# CM_Nightfall-Air_v1.net
KiCad netlist of a schematic drawn in EAGLE
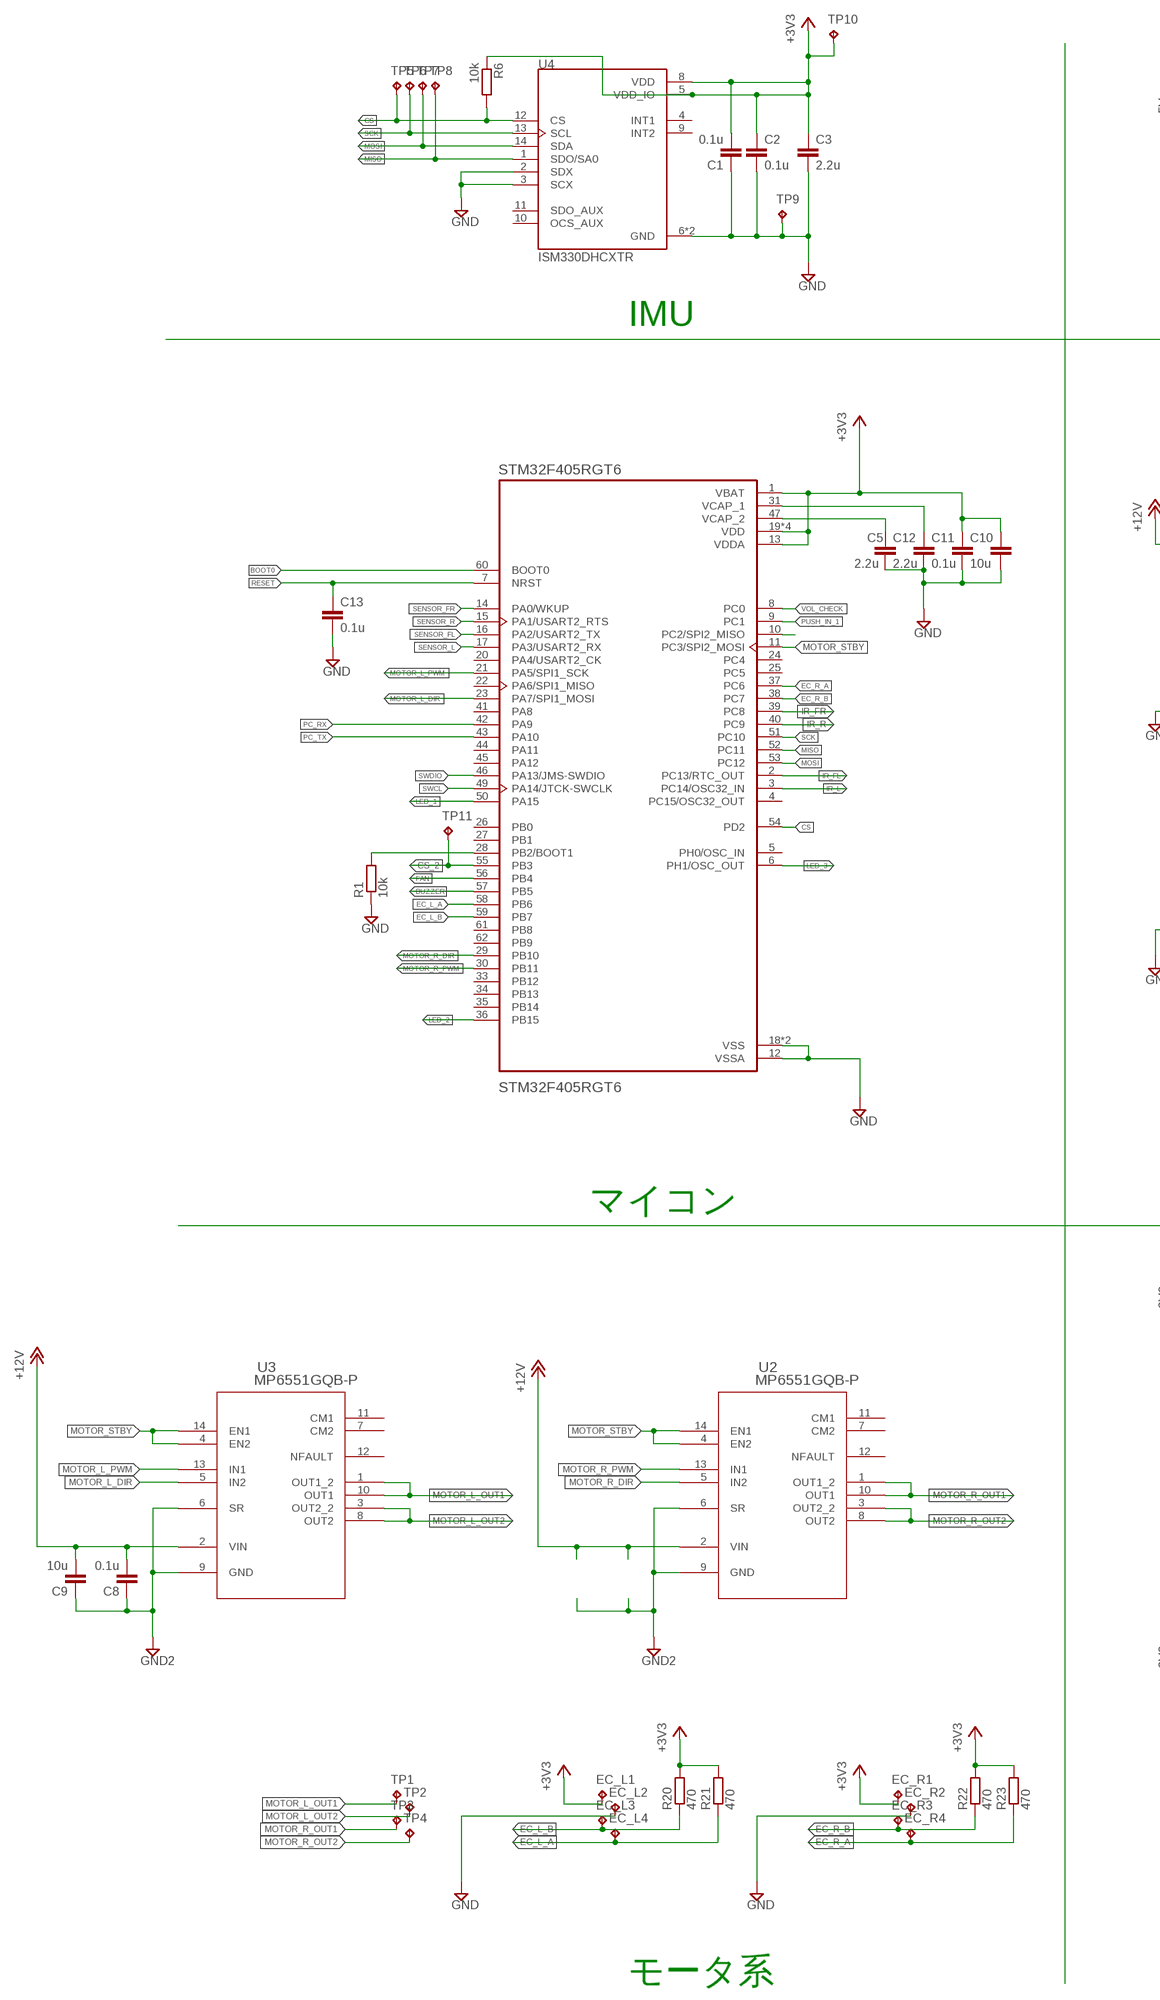
[diagram p0: schematic, sheet 1, part 1 of 2]
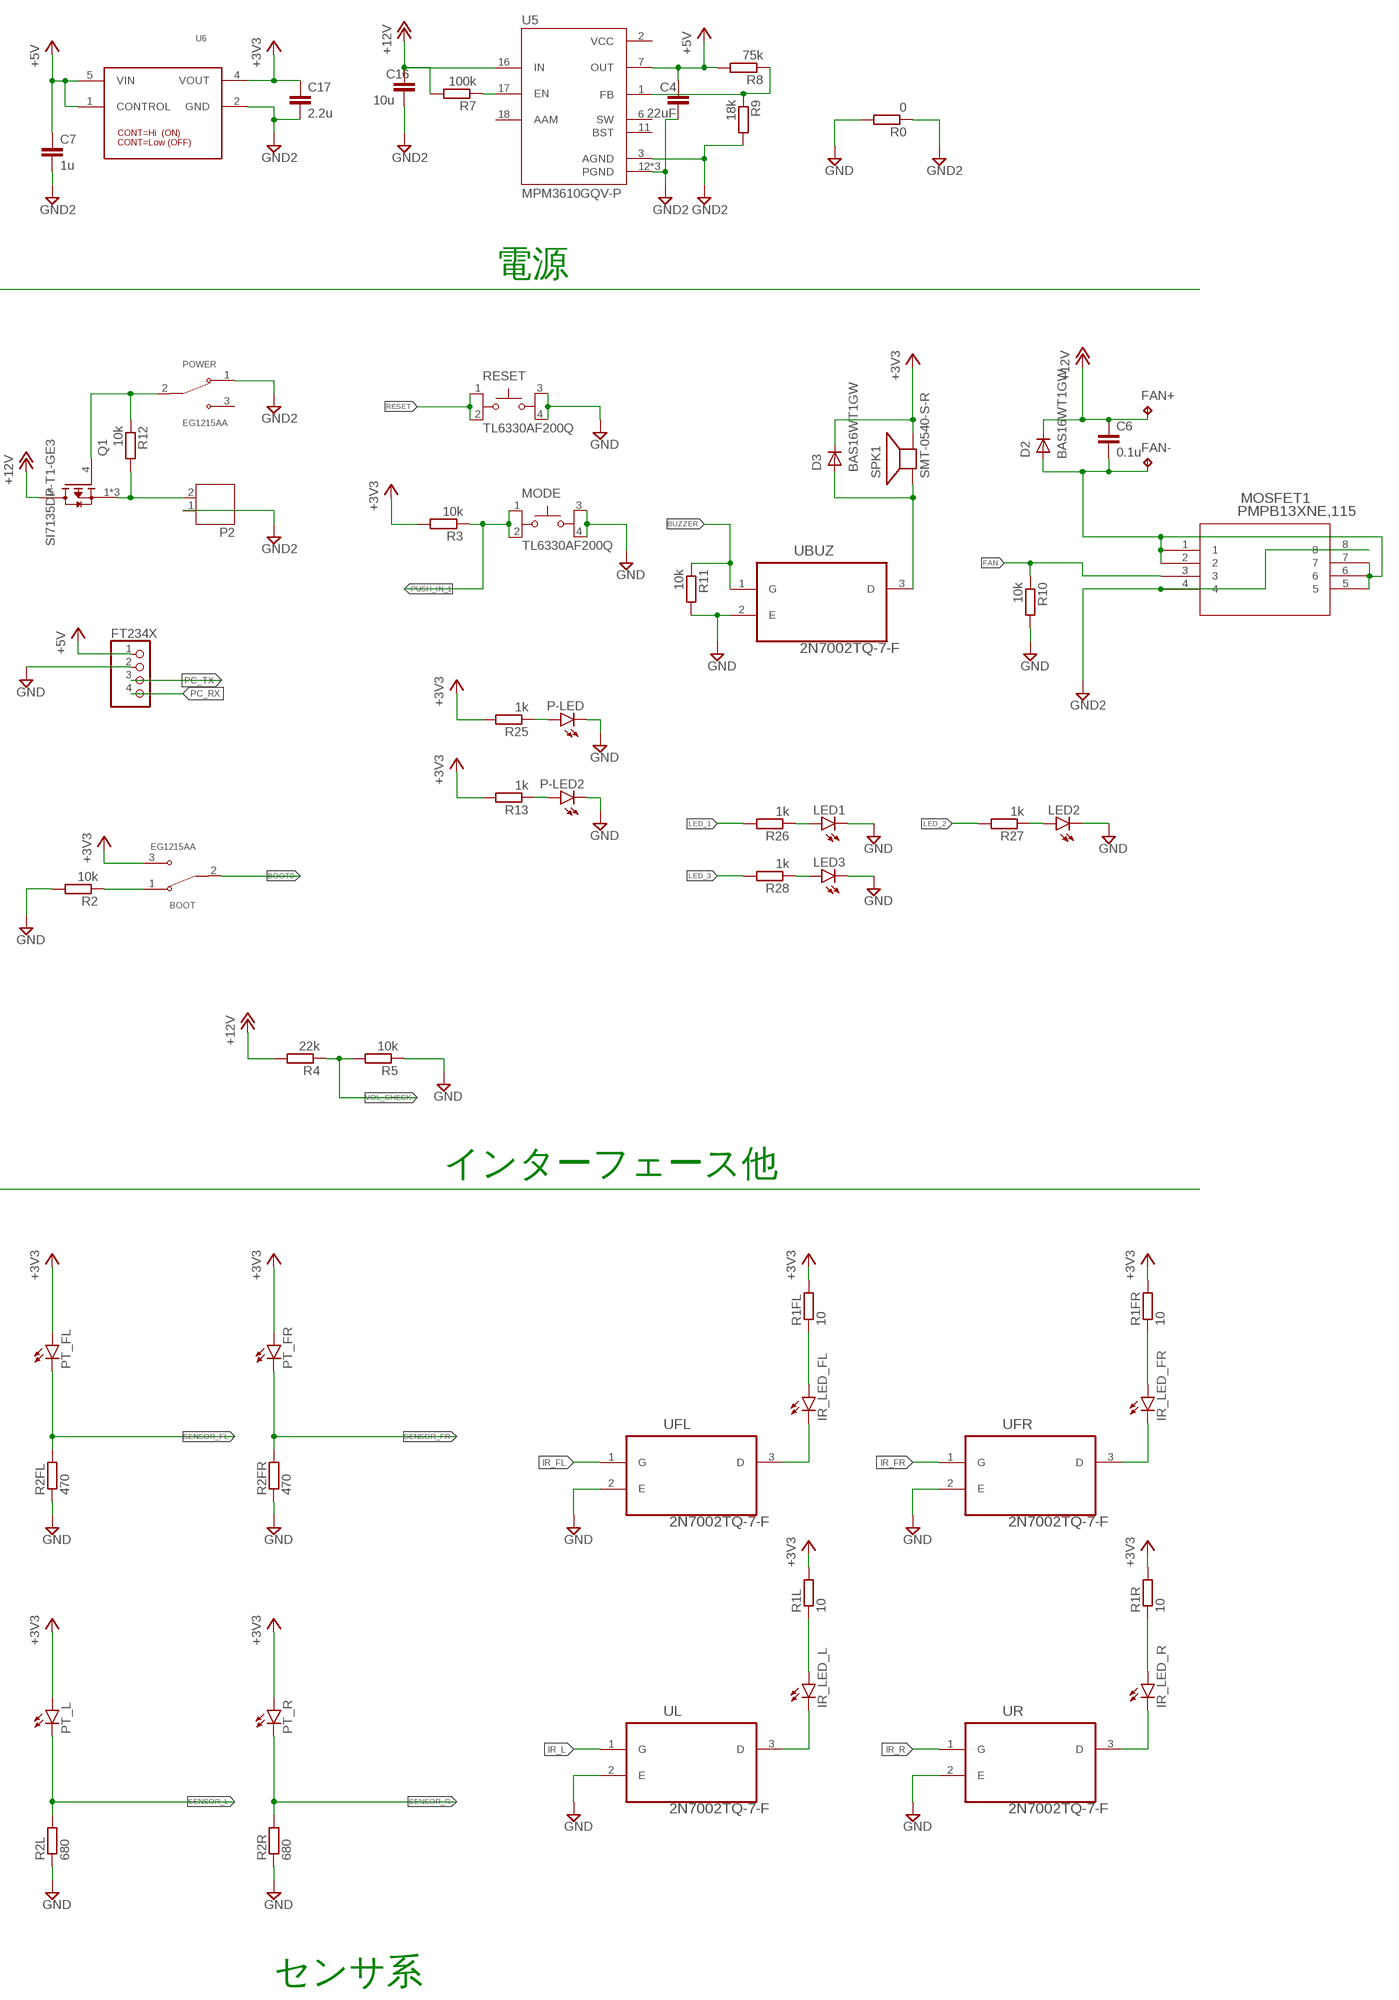
[diagram p1: schematic, sheet 1, part 2 of 2]

(export (version "E")
  (design (tool "Eeschema 10.0.6"))
  (components
    (comp (ref "BOOT")
      (value "EG1215AA")
      (footprint "eagle-import:SW_EG1215AA")
      (fields (field (name "MF") "E-Switch"))
      (libsource (lib "eagle-import") (part "EG1215AA"))
    )
    (comp (ref "C1")
      (value "0.1u")
      (footprint "eagle-import:C0402")
      (libsource (lib "eagle-import") (part "C-EUC0402"))
    )
    (comp (ref "C2")
      (value "0.1u")
      (footprint "eagle-import:C0402")
      (libsource (lib "eagle-import") (part "C-EUC0402"))
    )
    (comp (ref "C3")
      (value "2.2u")
      (footprint "eagle-import:C0402")
      (libsource (lib "eagle-import") (part "C-EUC0402"))
    )
    (comp (ref "C4")
      (value "22uF")
      (footprint "eagle-import:C0402")
      (libsource (lib "eagle-import") (part "C-EUC0402"))
    )
    (comp (ref "C5")
      (value "2.2u")
      (footprint "eagle-import:C0402")
      (libsource (lib "eagle-import") (part "C-EUC0402"))
    )
    (comp (ref "C6")
      (value "0.1u")
      (footprint "eagle-import:C0402")
      (libsource (lib "eagle-import") (part "C-EUC0402"))
    )
    (comp (ref "C7")
      (value "1u")
      (footprint "eagle-import:C0402")
      (libsource (lib "eagle-import") (part "C-EUC0402"))
    )
    (comp (ref "C8")
      (value "0.1u")
      (footprint "eagle-import:C0402")
      (libsource (lib "eagle-import") (part "C-EUC0402"))
    )
    (comp (ref "C9")
      (value "10u")
      (footprint "eagle-import:C0402")
      (libsource (lib "eagle-import") (part "C-EUC0402"))
    )
    (comp (ref "C10")
      (value "10u")
      (footprint "eagle-import:C0402")
      (libsource (lib "eagle-import") (part "C-EUC0402"))
    )
    (comp (ref "C11")
      (value "0.1u")
      (footprint "eagle-import:C0402")
      (libsource (lib "eagle-import") (part "C-EUC0402"))
    )
    (comp (ref "C12")
      (value "2.2u")
      (footprint "eagle-import:C0402")
      (libsource (lib "eagle-import") (part "C-EUC0402"))
    )
    (comp (ref "C13")
      (value "0.1u")
      (footprint "eagle-import:C0402")
      (libsource (lib "eagle-import") (part "C-EUC0402"))
    )
    (comp (ref "C16")
      (value "10u")
      (footprint "eagle-import:C0402")
      (libsource (lib "eagle-import") (part "C-EUC0402"))
    )
    (comp (ref "C17")
      (value "2.2u")
      (footprint "eagle-import:C0402")
      (libsource (lib "eagle-import") (part "C-EUC0402"))
    )
    (comp (ref "D2")
      (value "BAS16WT1GW")
      (footprint "eagle-import:SOT323")
      (fields (field (name "MF") "ON Semiconductor") (field (name "MP") "BAS16WT1G"))
      (libsource (lib "eagle-import") (part "BAS16WT1GW"))
    )
    (comp (ref "D3")
      (value "BAS16WT1GW")
      (footprint "eagle-import:SOT323")
      (fields (field (name "MF") "ON Semiconductor") (field (name "MP") "BAS16WT1G"))
      (libsource (lib "eagle-import") (part "BAS16WT1GW"))
    )
    (comp (ref "EC_L1")
      (value "TPB1,27")
      (footprint "eagle-import:B1,27")
      (libsource (lib "eagle-import") (part "TPB1,27"))
    )
    (comp (ref "EC_L2")
      (value "TPB1,27")
      (footprint "eagle-import:B1,27")
      (libsource (lib "eagle-import") (part "TPB1,27"))
    )
    (comp (ref "EC_L3")
      (value "TPB1,27")
      (footprint "eagle-import:B1,27")
      (libsource (lib "eagle-import") (part "TPB1,27"))
    )
    (comp (ref "EC_L4")
      (value "TPB1,27")
      (footprint "eagle-import:B1,27")
      (libsource (lib "eagle-import") (part "TPB1,27"))
    )
    (comp (ref "EC_R1")
      (value "TPB1,27")
      (footprint "eagle-import:B1,27")
      (libsource (lib "eagle-import") (part "TPB1,27"))
    )
    (comp (ref "EC_R2")
      (value "TPB1,27")
      (footprint "eagle-import:B1,27")
      (libsource (lib "eagle-import") (part "TPB1,27"))
    )
    (comp (ref "EC_R3")
      (value "TPB1,27")
      (footprint "eagle-import:B1,27")
      (libsource (lib "eagle-import") (part "TPB1,27"))
    )
    (comp (ref "EC_R4")
      (value "TPB1,27")
      (footprint "eagle-import:B1,27")
      (libsource (lib "eagle-import") (part "TPB1,27"))
    )
    (comp (ref "FAN+")
      (value "TPB1,27")
      (footprint "eagle-import:B1,27")
      (libsource (lib "eagle-import") (part "TPB1,27"))
    )
    (comp (ref "FAN-")
      (value "TPB1,27")
      (footprint "eagle-import:B1,27")
      (libsource (lib "eagle-import") (part "TPB1,27"))
    )
    (comp (ref "FT234X")
      (value "PINHD-1X4")
      (footprint "eagle-import:1X04")
      (libsource (lib "eagle-import") (part "PINHD-1X4"))
    )
    (comp (ref "IR_LED_FL")
      (value "LED5MM")
      (footprint "eagle-import:LED5MM")
      (libsource (lib "eagle-import") (part "LED5MM"))
    )
    (comp (ref "IR_LED_FR")
      (value "LED5MM")
      (footprint "eagle-import:LED5MM")
      (libsource (lib "eagle-import") (part "LED5MM"))
    )
    (comp (ref "IR_LED_L")
      (value "LED5MM")
      (footprint "eagle-import:LED5MM")
      (libsource (lib "eagle-import") (part "LED5MM"))
    )
    (comp (ref "IR_LED_R")
      (value "LED5MM")
      (footprint "eagle-import:LED5MM")
      (libsource (lib "eagle-import") (part "LED5MM"))
    )
    (comp (ref "LED1")
      (value "LEDCHIPLED_0603")
      (footprint "eagle-import:CHIPLED_0603")
      (libsource (lib "eagle-import") (part "LEDCHIPLED_0603"))
    )
    (comp (ref "LED2")
      (value "LEDCHIPLED_0603")
      (footprint "eagle-import:CHIPLED_0603")
      (libsource (lib "eagle-import") (part "LEDCHIPLED_0603"))
    )
    (comp (ref "LED3")
      (value "LEDCHIPLED_0603")
      (footprint "eagle-import:CHIPLED_0603")
      (libsource (lib "eagle-import") (part "LEDCHIPLED_0603"))
    )
    (comp (ref "MODE")
      (value "TL6330AF200Q")
      (footprint "eagle-import:SW_TL6330AF200Q")
      (fields (field (name "MF") "E-Switch"))
      (libsource (lib "eagle-import") (part "TL6330AF200Q"))
    )
    (comp (ref "MOSFET1")
      (value "PMPB13XNE,115")
      (footprint "eagle-import:DFN2020MD-6_SOT1220_NEX")
      (fields (field (name "COPYRIGHT") "Copyright (C) 2025 Ultra Librarian. All rights reserved."))
      (libsource (lib "eagle-import") (part "PMPB13XNE,115"))
    )
    (comp (ref "P-LED")
      (value "LEDCHIPLED_0603")
      (footprint "eagle-import:CHIPLED_0603")
      (libsource (lib "eagle-import") (part "LEDCHIPLED_0603"))
    )
    (comp (ref "P-LED2")
      (value "LEDCHIPLED_0603")
      (footprint "eagle-import:CHIPLED_0603")
      (libsource (lib "eagle-import") (part "LEDCHIPLED_0603"))
    )
    (comp (ref "P2")
      (value "JST-PH2")
      (footprint "eagle-import:JST-PH2")
      (libsource (lib "eagle-import") (part "JST-PH2"))
    )
    (comp (ref "POWER")
      (value "EG1215AA")
      (footprint "eagle-import:SW_EG1215AA")
      (fields (field (name "MF") "E-Switch"))
      (libsource (lib "eagle-import") (part "EG1215AA"))
    )
    (comp (ref "PT_FL")
      (value "LED5MM")
      (footprint "eagle-import:LED5MM")
      (libsource (lib "eagle-import") (part "LED5MM"))
    )
    (comp (ref "PT_FR")
      (value "LED5MM")
      (footprint "eagle-import:LED5MM")
      (libsource (lib "eagle-import") (part "LED5MM"))
    )
    (comp (ref "PT_L")
      (value "LED5MM")
      (footprint "eagle-import:LED5MM")
      (libsource (lib "eagle-import") (part "LED5MM"))
    )
    (comp (ref "PT_R")
      (value "LED5MM")
      (footprint "eagle-import:LED5MM")
      (libsource (lib "eagle-import") (part "LED5MM"))
    )
    (comp (ref "Q1")
      (value "SI7135DP-T1-GE3")
      (footprint "eagle-import:TRANS_SI7135DP-T1-GE3")
      (fields (field (name "MANUFACTURER") "Vishay Siliconix"))
      (libsource (lib "eagle-import") (part "SI7135DP-T1-GE3"))
    )
    (comp (ref "R0")
      (value "0")
      (footprint "eagle-import:R0402")
      (libsource (lib "eagle-import") (part "R-EU_R0402"))
    )
    (comp (ref "R1")
      (value "10k")
      (footprint "eagle-import:R0402")
      (libsource (lib "eagle-import") (part "R-EU_R0402"))
    )
    (comp (ref "R1FL")
      (value "10")
      (footprint "eagle-import:R0402")
      (libsource (lib "eagle-import") (part "R-EU_R0402"))
    )
    (comp (ref "R1FR")
      (value "10")
      (footprint "eagle-import:R0402")
      (libsource (lib "eagle-import") (part "R-EU_R0402"))
    )
    (comp (ref "R1L")
      (value "10")
      (footprint "eagle-import:R0402")
      (libsource (lib "eagle-import") (part "R-EU_R0402"))
    )
    (comp (ref "R1R")
      (value "10")
      (footprint "eagle-import:R0402")
      (libsource (lib "eagle-import") (part "R-EU_R0402"))
    )
    (comp (ref "R2")
      (value "10k")
      (footprint "eagle-import:R0402")
      (libsource (lib "eagle-import") (part "R-EU_R0402"))
    )
    (comp (ref "R2FL")
      (value "470")
      (footprint "eagle-import:R0402")
      (libsource (lib "eagle-import") (part "R-EU_R0402"))
    )
    (comp (ref "R2FR")
      (value "470")
      (footprint "eagle-import:R0402")
      (libsource (lib "eagle-import") (part "R-EU_R0402"))
    )
    (comp (ref "R2L")
      (value "680")
      (footprint "eagle-import:R0402")
      (libsource (lib "eagle-import") (part "R-EU_R0402"))
    )
    (comp (ref "R2R")
      (value "680")
      (footprint "eagle-import:R0402")
      (libsource (lib "eagle-import") (part "R-EU_R0402"))
    )
    (comp (ref "R3")
      (value "10k")
      (footprint "eagle-import:R0402")
      (libsource (lib "eagle-import") (part "R-EU_R0402"))
    )
    (comp (ref "R4")
      (value "22k")
      (footprint "eagle-import:R0402")
      (libsource (lib "eagle-import") (part "R-EU_R0402"))
    )
    (comp (ref "R5")
      (value "10k")
      (footprint "eagle-import:R0402")
      (libsource (lib "eagle-import") (part "R-EU_R0402"))
    )
    (comp (ref "R6")
      (value "10k")
      (footprint "eagle-import:R0402")
      (libsource (lib "eagle-import") (part "R-EU_R0402"))
    )
    (comp (ref "R7")
      (value "100k")
      (footprint "eagle-import:R0402")
      (libsource (lib "eagle-import") (part "R-EU_R0402"))
    )
    (comp (ref "R8")
      (value "75k")
      (footprint "eagle-import:R0402")
      (libsource (lib "eagle-import") (part "R-EU_R0402"))
    )
    (comp (ref "R9")
      (value "18k")
      (footprint "eagle-import:R0402")
      (libsource (lib "eagle-import") (part "R-EU_R0402"))
    )
    (comp (ref "R10")
      (value "10k")
      (footprint "eagle-import:R0402")
      (libsource (lib "eagle-import") (part "R-EU_R0402"))
    )
    (comp (ref "R11")
      (value "10k")
      (footprint "eagle-import:R0402")
      (libsource (lib "eagle-import") (part "R-EU_R0402"))
    )
    (comp (ref "R12")
      (value "10k")
      (footprint "eagle-import:R0402")
      (libsource (lib "eagle-import") (part "R-EU_R0402"))
    )
    (comp (ref "R13")
      (value "1k")
      (footprint "eagle-import:R0402")
      (libsource (lib "eagle-import") (part "R-EU_R0402"))
    )
    (comp (ref "R20")
      (value "470")
      (footprint "eagle-import:R0402")
      (libsource (lib "eagle-import") (part "R-EU_R0402"))
    )
    (comp (ref "R21")
      (value "470")
      (footprint "eagle-import:R0402")
      (libsource (lib "eagle-import") (part "R-EU_R0402"))
    )
    (comp (ref "R22")
      (value "470")
      (footprint "eagle-import:R0402")
      (libsource (lib "eagle-import") (part "R-EU_R0402"))
    )
    (comp (ref "R23")
      (value "470")
      (footprint "eagle-import:R0402")
      (libsource (lib "eagle-import") (part "R-EU_R0402"))
    )
    (comp (ref "R25")
      (value "1k")
      (footprint "eagle-import:R0402")
      (libsource (lib "eagle-import") (part "R-EU_R0402"))
    )
    (comp (ref "R26")
      (value "1k")
      (footprint "eagle-import:R0402")
      (libsource (lib "eagle-import") (part "R-EU_R0402"))
    )
    (comp (ref "R27")
      (value "1k")
      (footprint "eagle-import:R0402")
      (libsource (lib "eagle-import") (part "R-EU_R0402"))
    )
    (comp (ref "R28")
      (value "1k")
      (footprint "eagle-import:R0402")
      (libsource (lib "eagle-import") (part "R-EU_R0402"))
    )
    (comp (ref "RESET")
      (value "TL6330AF200Q")
      (footprint "eagle-import:SW_TL6330AF200Q")
      (fields (field (name "MF") "E-Switch"))
      (libsource (lib "eagle-import") (part "TL6330AF200Q"))
    )
    (comp (ref "SPK1")
      (value "SMT-0540-S-R")
      (footprint "eagle-import:SMT-0540-S-R")
      (fields (field (name "DIGI-KEY_PART_NUMBER") "668-1060-1-ND") (field (name "MF") "PUI"))
      (libsource (lib "eagle-import") (part "SMT-0540-S-R"))
    )
    (comp (ref "STM32F405RGT6")
      (value "STM32F405RGT6")
      (footprint "eagle-import:QFP50P1200X1200X160-64N")
      (fields (field (name "MF") "STMicroelectronics"))
      (libsource (lib "eagle-import") (part "STM32F405RGT6"))
    )
    (comp (ref "TP1")
      (value "TPB1,27")
      (footprint "eagle-import:B1,27")
      (libsource (lib "eagle-import") (part "TPB1,27"))
    )
    (comp (ref "TP2")
      (value "TPB1,27")
      (footprint "eagle-import:B1,27")
      (libsource (lib "eagle-import") (part "TPB1,27"))
    )
    (comp (ref "TP3")
      (value "TPB1,27")
      (footprint "eagle-import:B1,27")
      (libsource (lib "eagle-import") (part "TPB1,27"))
    )
    (comp (ref "TP4")
      (value "TPB1,27")
      (footprint "eagle-import:B1,27")
      (libsource (lib "eagle-import") (part "TPB1,27"))
    )
    (comp (ref "TP5")
      (value "TPTP06R")
      (footprint "eagle-import:TP06R")
      (libsource (lib "eagle-import") (part "TPTP06R"))
    )
    (comp (ref "TP6")
      (value "TPTP06R")
      (footprint "eagle-import:TP06R")
      (libsource (lib "eagle-import") (part "TPTP06R"))
    )
    (comp (ref "TP7")
      (value "TPTP06R")
      (footprint "eagle-import:TP06R")
      (libsource (lib "eagle-import") (part "TPTP06R"))
    )
    (comp (ref "TP8")
      (value "TPTP06R")
      (footprint "eagle-import:TP06R")
      (libsource (lib "eagle-import") (part "TPTP06R"))
    )
    (comp (ref "TP9")
      (value "TPTP06R")
      (footprint "eagle-import:TP06R")
      (libsource (lib "eagle-import") (part "TPTP06R"))
    )
    (comp (ref "TP10")
      (value "TPTP06R")
      (footprint "eagle-import:TP06R")
      (libsource (lib "eagle-import") (part "TPTP06R"))
    )
    (comp (ref "TP11")
      (value "TPTP06R")
      (footprint "eagle-import:TP06R")
      (libsource (lib "eagle-import") (part "TPTP06R"))
    )
    (comp (ref "U2")
      (value "MP6551GQB-P")
      (footprint "eagle-import:QFN-14_MP6551_MNP")
      (fields (field (name "COPYRIGHT") "Copyright (C) 2025 Ultra Librarian. All rights reserved."))
      (libsource (lib "eagle-import") (part "MP6551GQB-P"))
    )
    (comp (ref "U3")
      (value "MP6551GQB-P")
      (footprint "eagle-import:QFN-14_MP6551_MNP")
      (fields (field (name "COPYRIGHT") "Copyright (C) 2025 Ultra Librarian. All rights reserved."))
      (libsource (lib "eagle-import") (part "MP6551GQB-P"))
    )
    (comp (ref "U4")
      (value "ISM330DHCXTR")
      (footprint "eagle-import:PQFN50P250X300X86-14N")
      (fields (field (name "MF") "STMicroelectronics"))
      (libsource (lib "eagle-import") (part "ISM330DHCXTR"))
    )
    (comp (ref "U5")
      (value "MPM3610GQV-P")
      (footprint "eagle-import:CONV_MPM3610GQV-P")
      (fields (field (name "MF") "Monolithic Power Systems") (field (name "MP") "MPM3610GQVP"))
      (libsource (lib "eagle-import") (part "MPM3610GQV-P"))
    )
    (comp (ref "U6")
      (value "I-10673_NJM2884U1-33")
      (footprint "eagle-import:NJM2884U1-33")
      (libsource (lib "eagle-import") (part "I-10673_NJM2884U1-33"))
    )
    (comp (ref "UBUZ")
      (value "2N7002TQ-7-F")
      (footprint "eagle-import:SOT50P160X90-3N")
      (fields (field (name "MF") "Diodes Inc."))
      (libsource (lib "eagle-import") (part "2N7002TQ-7-F"))
    )
    (comp (ref "UFL")
      (value "2N7002TQ-7-F")
      (footprint "eagle-import:SOT50P160X90-3N")
      (fields (field (name "MF") "Diodes Inc."))
      (libsource (lib "eagle-import") (part "2N7002TQ-7-F"))
    )
    (comp (ref "UFR")
      (value "2N7002TQ-7-F")
      (footprint "eagle-import:SOT50P160X90-3N")
      (fields (field (name "MF") "Diodes Inc."))
      (libsource (lib "eagle-import") (part "2N7002TQ-7-F"))
    )
    (comp (ref "UL")
      (value "2N7002TQ-7-F")
      (footprint "eagle-import:SOT50P160X90-3N")
      (fields (field (name "MF") "Diodes Inc."))
      (libsource (lib "eagle-import") (part "2N7002TQ-7-F"))
    )
    (comp (ref "UR")
      (value "2N7002TQ-7-F")
      (footprint "eagle-import:SOT50P160X90-3N")
      (fields (field (name "MF") "Diodes Inc."))
      (libsource (lib "eagle-import") (part "2N7002TQ-7-F"))
    )
  )
  (nets
    (net (code "1") (name "+3V3") (class "Default")
      (node (ref "BOOT") (pin "3") (pinfunction "3_3") (pintype "passive"))
      (node (ref "C1") (pin "2") (pinfunction "2_2") (pintype "passive"))
      (node (ref "C10") (pin "1") (pinfunction "1_1") (pintype "passive"))
      (node (ref "C11") (pin "1") (pinfunction "1_1") (pintype "passive"))
      (node (ref "C17") (pin "1") (pinfunction "1_1") (pintype "passive"))
      (node (ref "C2") (pin "1") (pinfunction "1_1") (pintype "passive"))
      (node (ref "C3") (pin "1") (pinfunction "1_1") (pintype "passive"))
      (node (ref "D3") (pin "3") (pinfunction "K_3") (pintype "passive"))
      (node (ref "EC_L1") (pin "TP") (pinfunction "TP_TP") (pintype "input"))
      (node (ref "EC_R1") (pin "TP") (pinfunction "TP_TP") (pintype "input"))
      (node (ref "PT_FL") (pin "A") (pinfunction "A_A") (pintype "passive"))
      (node (ref "PT_FR") (pin "A") (pinfunction "A_A") (pintype "passive"))
      (node (ref "PT_L") (pin "A") (pinfunction "A_A") (pintype "passive"))
      (node (ref "PT_R") (pin "A") (pinfunction "A_A") (pintype "passive"))
      (node (ref "R13") (pin "2") (pinfunction "2_2") (pintype "passive"))
      (node (ref "R1FL") (pin "2") (pinfunction "2_2") (pintype "passive"))
      (node (ref "R1FR") (pin "2") (pinfunction "2_2") (pintype "passive"))
      (node (ref "R1L") (pin "2") (pinfunction "2_2") (pintype "passive"))
      (node (ref "R1R") (pin "2") (pinfunction "2_2") (pintype "passive"))
      (node (ref "R20") (pin "2") (pinfunction "2_2") (pintype "passive"))
      (node (ref "R21") (pin "2") (pinfunction "2_2") (pintype "passive"))
      (node (ref "R22") (pin "2") (pinfunction "2_2") (pintype "passive"))
      (node (ref "R23") (pin "2") (pinfunction "2_2") (pintype "passive"))
      (node (ref "R25") (pin "2") (pinfunction "2_2") (pintype "passive"))
      (node (ref "R3") (pin "2") (pinfunction "2_2") (pintype "passive"))
      (node (ref "R6") (pin "1") (pinfunction "1_1") (pintype "passive"))
      (node (ref "SPK1") (pin "+") (pinfunction "-_+") (pintype "passive"))
      (node (ref "STM32F405RGT6") (pin "1") (pinfunction "VBAT_1") (pintype "power_in"))
      (node (ref "STM32F405RGT6") (pin "13") (pinfunction "VDDA_13") (pintype "power_in"))
      (node (ref "STM32F405RGT6") (pin "19") (pinfunction "VDD_19") (pintype "power_in"))
      (node (ref "STM32F405RGT6") (pin "32") (pinfunction "VDD_32") (pintype "power_in"))
      (node (ref "STM32F405RGT6") (pin "48") (pinfunction "VDD_48") (pintype "power_in"))
      (node (ref "STM32F405RGT6") (pin "64") (pinfunction "VDD_64") (pintype "power_in"))
      (node (ref "TP10") (pin "TP") (pinfunction "TP_TP") (pintype "input"))
      (node (ref "U4") (pin "5") (pinfunction "VDD_IO_5") (pintype "power_in"))
      (node (ref "U4") (pin "8") (pinfunction "VDD_8") (pintype "power_in"))
      (node (ref "U6") (pin "4") (pinfunction "VOUT_4") (pintype "bidirectional"))
    )
    (net (code "2") (name "+5V") (class "Default")
      (node (ref "C4") (pin "1") (pinfunction "1_1") (pintype "passive"))
      (node (ref "C7") (pin "1") (pinfunction "1_1") (pintype "passive"))
      (node (ref "FT234X") (pin "1") (pinfunction "1_1") (pintype "passive"))
      (node (ref "R8") (pin "2") (pinfunction "2_2") (pintype "passive"))
      (node (ref "U5") (pin "7") (pinfunction "OUT_7") (pintype "output"))
      (node (ref "U6") (pin "1") (pinfunction "CONTROL_1") (pintype "bidirectional"))
      (node (ref "U6") (pin "5") (pinfunction "VIN_5") (pintype "bidirectional"))
    )
    (net (code "3") (name "+12V") (class "Default")
      (node (ref "C16") (pin "1") (pinfunction "1_1") (pintype "passive"))
      (node (ref "C6") (pin "1") (pinfunction "1_1") (pintype "passive"))
      (node (ref "C8") (pin "2") (pinfunction "2_2") (pintype "passive"))
      (node (ref "C9") (pin "2") (pinfunction "2_2") (pintype "passive"))
      (node (ref "D2") (pin "3") (pinfunction "K_3") (pintype "passive"))
      (node (ref "FAN+") (pin "TP") (pinfunction "TP_TP") (pintype "input"))
      (node (ref "Q1") (pin "5") (pinfunction "D_5") (pintype "passive"))
      (node (ref "R4") (pin "2") (pinfunction "2_2") (pintype "passive"))
      (node (ref "R7") (pin "2") (pinfunction "2_2") (pintype "passive"))
      (node (ref "U2") (pin "2") (pinfunction "VIN_2") (pintype "power_in"))
      (node (ref "U3") (pin "2") (pinfunction "VIN_2") (pintype "power_in"))
      (node (ref "U5") (pin "16") (pinfunction "IN_16") (pintype "input"))
    )
    (net (code "4") (name "/VCC") (class "Default")
      (node (ref "U5") (pin "2") (pinfunction "VCC_2") (pintype "power_in"))
    )
    (net (code "5") (name "BOOT0") (class "Default")
      (node (ref "BOOT") (pin "2") (pinfunction "2_2") (pintype "passive"))
      (node (ref "STM32F405RGT6") (pin "60") (pinfunction "BOOT0_60") (pintype "bidirectional"))
    )
    (net (code "6") (name "BUZZER") (class "Default")
      (node (ref "R11") (pin "1") (pinfunction "1_1") (pintype "passive"))
      (node (ref "STM32F405RGT6") (pin "57") (pinfunction "PB5_57") (pintype "bidirectional"))
      (node (ref "UBUZ") (pin "1") (pinfunction "G_1") (pintype "passive"))
    )
    (net (code "7") (name "CS") (class "Default")
      (node (ref "R6") (pin "2") (pinfunction "2_2") (pintype "passive"))
      (node (ref "STM32F405RGT6") (pin "54") (pinfunction "PD2_54") (pintype "bidirectional"))
      (node (ref "TP5") (pin "TP") (pinfunction "TP_TP") (pintype "input"))
      (node (ref "U4") (pin "12") (pinfunction "CS_12") (pintype "input"))
    )
    (net (code "8") (name "CS_2") (class "Default")
      (node (ref "STM32F405RGT6") (pin "55") (pinfunction "PB3_55") (pintype "bidirectional"))
      (node (ref "TP11") (pin "TP") (pinfunction "TP_TP") (pintype "input"))
    )
    (net (code "9") (name "EC_L_A") (class "Default")
      (node (ref "EC_L4") (pin "TP") (pinfunction "TP_TP") (pintype "input"))
      (node (ref "R21") (pin "1") (pinfunction "1_1") (pintype "passive"))
      (node (ref "STM32F405RGT6") (pin "58") (pinfunction "PB6_58") (pintype "bidirectional"))
    )
    (net (code "10") (name "EC_L_B") (class "Default")
      (node (ref "EC_L3") (pin "TP") (pinfunction "TP_TP") (pintype "input"))
      (node (ref "R20") (pin "1") (pinfunction "1_1") (pintype "passive"))
      (node (ref "STM32F405RGT6") (pin "59") (pinfunction "PB7_59") (pintype "bidirectional"))
    )
    (net (code "11") (name "EC_R_A") (class "Default")
      (node (ref "EC_R4") (pin "TP") (pinfunction "TP_TP") (pintype "input"))
      (node (ref "R23") (pin "1") (pinfunction "1_1") (pintype "passive"))
      (node (ref "STM32F405RGT6") (pin "37") (pinfunction "PC6_37") (pintype "bidirectional"))
    )
    (net (code "12") (name "EC_R_B") (class "Default")
      (node (ref "EC_R3") (pin "TP") (pinfunction "TP_TP") (pintype "input"))
      (node (ref "R22") (pin "1") (pinfunction "1_1") (pintype "passive"))
      (node (ref "STM32F405RGT6") (pin "38") (pinfunction "PC7_38") (pintype "bidirectional"))
    )
    (net (code "13") (name "FAN") (class "Default")
      (node (ref "MOSFET1") (pin "3") (pinfunction "3_3") (pintype "passive"))
      (node (ref "R10") (pin "1") (pinfunction "1_1") (pintype "passive"))
      (node (ref "STM32F405RGT6") (pin "56") (pinfunction "PB4_56") (pintype "bidirectional"))
    )
    (net (code "14") (name "GND") (class "Default")
      (node (ref "C1") (pin "1") (pinfunction "1_1") (pintype "passive"))
      (node (ref "C10") (pin "2") (pinfunction "2_2") (pintype "passive"))
      (node (ref "C11") (pin "2") (pinfunction "2_2") (pintype "passive"))
      (node (ref "C12") (pin "2") (pinfunction "2_2") (pintype "passive"))
      (node (ref "C13") (pin "2") (pinfunction "2_2") (pintype "passive"))
      (node (ref "C2") (pin "2") (pinfunction "2_2") (pintype "passive"))
      (node (ref "C3") (pin "2") (pinfunction "2_2") (pintype "passive"))
      (node (ref "C5") (pin "2") (pinfunction "2_2") (pintype "passive"))
      (node (ref "EC_L2") (pin "TP") (pinfunction "TP_TP") (pintype "input"))
      (node (ref "EC_R2") (pin "TP") (pinfunction "TP_TP") (pintype "input"))
      (node (ref "FT234X") (pin "2") (pinfunction "2_2") (pintype "passive"))
      (node (ref "LED1") (pin "C") (pinfunction "C_C") (pintype "passive"))
      (node (ref "LED2") (pin "C") (pinfunction "C_C") (pintype "passive"))
      (node (ref "LED3") (pin "C") (pinfunction "C_C") (pintype "passive"))
      (node (ref "MODE") (pin "3") (pinfunction "3_3") (pintype "passive"))
      (node (ref "MODE") (pin "4") (pinfunction "4_4") (pintype "passive"))
      (node (ref "P-LED") (pin "C") (pinfunction "C_C") (pintype "passive"))
      (node (ref "P-LED2") (pin "C") (pinfunction "C_C") (pintype "passive"))
      (node (ref "R0") (pin "2") (pinfunction "2_2") (pintype "passive"))
      (node (ref "R1") (pin "1") (pinfunction "1_1") (pintype "passive"))
      (node (ref "R10") (pin "2") (pinfunction "2_2") (pintype "passive"))
      (node (ref "R11") (pin "2") (pinfunction "2_2") (pintype "passive"))
      (node (ref "R2") (pin "2") (pinfunction "2_2") (pintype "passive"))
      (node (ref "R2FL") (pin "1") (pinfunction "1_1") (pintype "passive"))
      (node (ref "R2FR") (pin "1") (pinfunction "1_1") (pintype "passive"))
      (node (ref "R2L") (pin "1") (pinfunction "1_1") (pintype "passive"))
      (node (ref "R2R") (pin "1") (pinfunction "1_1") (pintype "passive"))
      (node (ref "R5") (pin "1") (pinfunction "1_1") (pintype "passive"))
      (node (ref "RESET") (pin "3") (pinfunction "3_3") (pintype "passive"))
      (node (ref "RESET") (pin "4") (pinfunction "4_4") (pintype "passive"))
      (node (ref "STM32F405RGT6") (pin "12") (pinfunction "VSSA_12") (pintype "power_in"))
      (node (ref "STM32F405RGT6") (pin "18") (pinfunction "VSS_18") (pintype "power_in"))
      (node (ref "STM32F405RGT6") (pin "63") (pinfunction "VSS_63") (pintype "power_in"))
      (node (ref "TP9") (pin "TP") (pinfunction "TP_TP") (pintype "input"))
      (node (ref "U4") (pin "2") (pinfunction "SDX_2") (pintype "bidirectional"))
      (node (ref "U4") (pin "3") (pinfunction "SCX_3") (pintype "bidirectional"))
      (node (ref "U4") (pin "6") (pinfunction "GND_6") (pintype "power_in"))
      (node (ref "U4") (pin "7") (pinfunction "GND_7") (pintype "power_in"))
      (node (ref "UBUZ") (pin "2") (pinfunction "E_2") (pintype "passive"))
      (node (ref "UFL") (pin "2") (pinfunction "E_2") (pintype "passive"))
      (node (ref "UFR") (pin "2") (pinfunction "E_2") (pintype "passive"))
      (node (ref "UL") (pin "2") (pinfunction "E_2") (pintype "passive"))
      (node (ref "UR") (pin "2") (pinfunction "E_2") (pintype "passive"))
    )
    (net (code "15") (name "GND2") (class "Default")
      (node (ref "C16") (pin "2") (pinfunction "2_2") (pintype "passive"))
      (node (ref "C17") (pin "2") (pinfunction "2_2") (pintype "passive"))
      (node (ref "C4") (pin "2") (pinfunction "2_2") (pintype "passive"))
      (node (ref "C7") (pin "2") (pinfunction "2_2") (pintype "passive"))
      (node (ref "C8") (pin "1") (pinfunction "1_1") (pintype "passive"))
      (node (ref "C9") (pin "1") (pinfunction "1_1") (pintype "passive"))
      (node (ref "MOSFET1") (pin "4") (pinfunction "4_4") (pintype "passive"))
      (node (ref "MOSFET1") (pin "8") (pinfunction "8_8") (pintype "passive"))
      (node (ref "P2") (pin "1") (pinfunction "1_1") (pintype "passive"))
      (node (ref "POWER") (pin "1") (pinfunction "1_1") (pintype "passive"))
      (node (ref "R0") (pin "1") (pinfunction "1_1") (pintype "passive"))
      (node (ref "R9") (pin "2") (pinfunction "2_2") (pintype "passive"))
      (node (ref "U2") (pin "6") (pinfunction "SR_6") (pintype "passive"))
      (node (ref "U2") (pin "9") (pinfunction "GND_9") (pintype "power_in"))
      (node (ref "U3") (pin "6") (pinfunction "SR_6") (pintype "passive"))
      (node (ref "U3") (pin "9") (pinfunction "GND_9") (pintype "power_in"))
      (node (ref "U5") (pin "12") (pinfunction "PGND_12") (pintype "power_in"))
      (node (ref "U5") (pin "13") (pinfunction "PGND_13") (pintype "power_in"))
      (node (ref "U5") (pin "14") (pinfunction "PGND_14") (pintype "power_in"))
      (node (ref "U5") (pin "3") (pinfunction "AGND_3") (pintype "power_in"))
      (node (ref "U6") (pin "2") (pinfunction "GND_2") (pintype "bidirectional"))
    )
    (net (code "16") (name "IR_FL") (class "Default")
      (node (ref "STM32F405RGT6") (pin "2") (pinfunction "PC13/RTC_OUT_2") (pintype "bidirectional"))
      (node (ref "UFL") (pin "1") (pinfunction "G_1") (pintype "passive"))
    )
    (net (code "17") (name "IR_FR") (class "Default")
      (node (ref "STM32F405RGT6") (pin "39") (pinfunction "PC8_39") (pintype "bidirectional"))
      (node (ref "UFR") (pin "1") (pinfunction "G_1") (pintype "passive"))
    )
    (net (code "18") (name "IR_L") (class "Default")
      (node (ref "STM32F405RGT6") (pin "3") (pinfunction "PC14/OSC32_IN_3") (pintype "bidirectional"))
      (node (ref "UL") (pin "1") (pinfunction "G_1") (pintype "passive"))
    )
    (net (code "19") (name "IR_R") (class "Default")
      (node (ref "STM32F405RGT6") (pin "40") (pinfunction "PC9_40") (pintype "bidirectional"))
      (node (ref "UR") (pin "1") (pinfunction "G_1") (pintype "passive"))
    )
    (net (code "20") (name "LED_1") (class "Default")
      (node (ref "R26") (pin "2") (pinfunction "2_2") (pintype "passive"))
      (node (ref "STM32F405RGT6") (pin "50") (pinfunction "PA15_50") (pintype "bidirectional"))
    )
    (net (code "21") (name "LED_2") (class "Default")
      (node (ref "R27") (pin "2") (pinfunction "2_2") (pintype "passive"))
      (node (ref "STM32F405RGT6") (pin "36") (pinfunction "PB15_36") (pintype "bidirectional"))
    )
    (net (code "22") (name "LED_3") (class "Default")
      (node (ref "R28") (pin "2") (pinfunction "2_2") (pintype "passive"))
      (node (ref "STM32F405RGT6") (pin "6") (pinfunction "PH1/OSC_OUT_6") (pintype "bidirectional"))
    )
    (net (code "23") (name "MISO") (class "Default")
      (node (ref "STM32F405RGT6") (pin "52") (pinfunction "PC11_52") (pintype "bidirectional"))
      (node (ref "TP8") (pin "TP") (pinfunction "TP_TP") (pintype "input"))
      (node (ref "U4") (pin "1") (pinfunction "SDO/SA0_1") (pintype "bidirectional"))
    )
    (net (code "24") (name "MOSI") (class "Default")
      (node (ref "STM32F405RGT6") (pin "53") (pinfunction "PC12_53") (pintype "bidirectional"))
      (node (ref "TP7") (pin "TP") (pinfunction "TP_TP") (pintype "input"))
      (node (ref "U4") (pin "14") (pinfunction "SDA_14") (pintype "bidirectional"))
    )
    (net (code "25") (name "MOTOR_L_DIR") (class "Default")
      (node (ref "STM32F405RGT6") (pin "23") (pinfunction "PA7/SPI1_MOSI_23") (pintype "bidirectional"))
      (node (ref "U3") (pin "5") (pinfunction "IN2_5") (pintype "input"))
    )
    (net (code "26") (name "MOTOR_L_OUT1") (class "Default")
      (node (ref "TP1") (pin "TP") (pinfunction "TP_TP") (pintype "input"))
      (node (ref "U3") (pin "1") (pinfunction "OUT1_2_1") (pintype "output"))
      (node (ref "U3") (pin "10") (pinfunction "OUT1_10") (pintype "output"))
    )
    (net (code "27") (name "MOTOR_L_OUT2") (class "Default")
      (node (ref "TP2") (pin "TP") (pinfunction "TP_TP") (pintype "input"))
      (node (ref "U3") (pin "3") (pinfunction "OUT2_2_3") (pintype "output"))
      (node (ref "U3") (pin "8") (pinfunction "OUT2_8") (pintype "output"))
    )
    (net (code "28") (name "MOTOR_L_PWM") (class "Default")
      (node (ref "STM32F405RGT6") (pin "21") (pinfunction "PA5/SPI1_SCK_21") (pintype "bidirectional"))
      (node (ref "U3") (pin "13") (pinfunction "IN1_13") (pintype "input"))
    )
    (net (code "29") (name "MOTOR_R_DIR") (class "Default")
      (node (ref "STM32F405RGT6") (pin "29") (pinfunction "PB10_29") (pintype "bidirectional"))
      (node (ref "U2") (pin "5") (pinfunction "IN2_5") (pintype "input"))
    )
    (net (code "30") (name "MOTOR_R_OUT1") (class "Default")
      (node (ref "TP3") (pin "TP") (pinfunction "TP_TP") (pintype "input"))
      (node (ref "U2") (pin "1") (pinfunction "OUT1_2_1") (pintype "output"))
      (node (ref "U2") (pin "10") (pinfunction "OUT1_10") (pintype "output"))
    )
    (net (code "31") (name "MOTOR_R_OUT2") (class "Default")
      (node (ref "TP4") (pin "TP") (pinfunction "TP_TP") (pintype "input"))
      (node (ref "U2") (pin "3") (pinfunction "OUT2_2_3") (pintype "output"))
      (node (ref "U2") (pin "8") (pinfunction "OUT2_8") (pintype "output"))
    )
    (net (code "32") (name "MOTOR_R_PWM") (class "Default")
      (node (ref "STM32F405RGT6") (pin "30") (pinfunction "PB11_30") (pintype "bidirectional"))
      (node (ref "U2") (pin "13") (pinfunction "IN1_13") (pintype "input"))
    )
    (net (code "33") (name "MOTOR_STBY") (class "Default")
      (node (ref "STM32F405RGT6") (pin "11") (pinfunction "PC3/SPI2_MOSI_11") (pintype "bidirectional"))
      (node (ref "U2") (pin "14") (pinfunction "EN1_14") (pintype "input"))
      (node (ref "U2") (pin "4") (pinfunction "EN2_4") (pintype "input"))
      (node (ref "U3") (pin "14") (pinfunction "EN1_14") (pintype "input"))
      (node (ref "U3") (pin "4") (pinfunction "EN2_4") (pintype "input"))
    )
    (net (code "34") (name "Net-(BOOT-Pad1)") (class "Default")
      (node (ref "BOOT") (pin "1") (pinfunction "1_1") (pintype "passive"))
      (node (ref "R2") (pin "1") (pinfunction "1_1") (pintype "passive"))
    )
    (net (code "35") (name "Net-(D2-A)") (class "Default")
      (node (ref "C6") (pin "2") (pinfunction "2_2") (pintype "passive"))
      (node (ref "D2") (pin "1") (pinfunction "A_1") (pintype "passive"))
      (node (ref "FAN-") (pin "TP") (pinfunction "TP_TP") (pintype "input"))
      (node (ref "MOSFET1") (pin "1") (pinfunction "1_1") (pintype "passive"))
      (node (ref "MOSFET1") (pin "2") (pinfunction "2_2") (pintype "passive"))
      (node (ref "MOSFET1") (pin "5") (pinfunction "5_5") (pintype "passive"))
      (node (ref "MOSFET1") (pin "6") (pinfunction "6_6") (pintype "passive"))
      (node (ref "MOSFET1") (pin "7") (pinfunction "7_7") (pintype "passive"))
    )
    (net (code "36") (name "Net-(D3-A)") (class "Default")
      (node (ref "D3") (pin "1") (pinfunction "A_1") (pintype "passive"))
      (node (ref "SPK1") (pin "-") (pinfunction "+_-") (pintype "passive"))
      (node (ref "UBUZ") (pin "3") (pinfunction "D_3") (pintype "passive"))
    )
    (net (code "37") (name "Net-(IR_LED_FL-C)") (class "Default")
      (node (ref "IR_LED_FL") (pin "K") (pinfunction "C_K") (pintype "passive"))
      (node (ref "UFL") (pin "3") (pinfunction "D_3") (pintype "passive"))
    )
    (net (code "38") (name "Net-(IR_LED_FL-PadA)") (class "Default")
      (node (ref "IR_LED_FL") (pin "A") (pinfunction "A_A") (pintype "passive"))
      (node (ref "R1FL") (pin "1") (pinfunction "1_1") (pintype "passive"))
    )
    (net (code "39") (name "Net-(IR_LED_FR-C)") (class "Default")
      (node (ref "IR_LED_FR") (pin "K") (pinfunction "C_K") (pintype "passive"))
      (node (ref "UFR") (pin "3") (pinfunction "D_3") (pintype "passive"))
    )
    (net (code "40") (name "Net-(IR_LED_FR-PadA)") (class "Default")
      (node (ref "IR_LED_FR") (pin "A") (pinfunction "A_A") (pintype "passive"))
      (node (ref "R1FR") (pin "1") (pinfunction "1_1") (pintype "passive"))
    )
    (net (code "41") (name "Net-(IR_LED_L-C)") (class "Default")
      (node (ref "IR_LED_L") (pin "K") (pinfunction "C_K") (pintype "passive"))
      (node (ref "UL") (pin "3") (pinfunction "D_3") (pintype "passive"))
    )
    (net (code "42") (name "Net-(IR_LED_L-PadA)") (class "Default")
      (node (ref "IR_LED_L") (pin "A") (pinfunction "A_A") (pintype "passive"))
      (node (ref "R1L") (pin "1") (pinfunction "1_1") (pintype "passive"))
    )
    (net (code "43") (name "Net-(IR_LED_R-C)") (class "Default")
      (node (ref "IR_LED_R") (pin "K") (pinfunction "C_K") (pintype "passive"))
      (node (ref "UR") (pin "3") (pinfunction "D_3") (pintype "passive"))
    )
    (net (code "44") (name "Net-(IR_LED_R-PadA)") (class "Default")
      (node (ref "IR_LED_R") (pin "A") (pinfunction "A_A") (pintype "passive"))
      (node (ref "R1R") (pin "1") (pinfunction "1_1") (pintype "passive"))
    )
    (net (code "45") (name "Net-(LED1-PadA)") (class "Default")
      (node (ref "LED1") (pin "A") (pinfunction "A_A") (pintype "passive"))
      (node (ref "R26") (pin "1") (pinfunction "1_1") (pintype "passive"))
    )
    (net (code "46") (name "Net-(LED2-PadA)") (class "Default")
      (node (ref "LED2") (pin "A") (pinfunction "A_A") (pintype "passive"))
      (node (ref "R27") (pin "1") (pinfunction "1_1") (pintype "passive"))
    )
    (net (code "47") (name "Net-(LED3-PadA)") (class "Default")
      (node (ref "LED3") (pin "A") (pinfunction "A_A") (pintype "passive"))
      (node (ref "R28") (pin "1") (pinfunction "1_1") (pintype "passive"))
    )
    (net (code "48") (name "Net-(P-LED-PadA)") (class "Default")
      (node (ref "P-LED") (pin "A") (pinfunction "A_A") (pintype "passive"))
      (node (ref "R25") (pin "1") (pinfunction "1_1") (pintype "passive"))
    )
    (net (code "49") (name "Net-(P-LED2-PadA)") (class "Default")
      (node (ref "P-LED2") (pin "A") (pinfunction "A_A") (pintype "passive"))
      (node (ref "R13") (pin "1") (pinfunction "1_1") (pintype "passive"))
    )
    (net (code "50") (name "Net-(P2-Pad2)") (class "Default")
      (node (ref "P2") (pin "2") (pinfunction "2_2") (pintype "passive"))
      (node (ref "Q1") (pin "1") (pinfunction "S_1") (pintype "passive"))
      (node (ref "Q1") (pin "2") (pinfunction "S_2") (pintype "passive"))
      (node (ref "Q1") (pin "3") (pinfunction "S_3") (pintype "passive"))
      (node (ref "R12") (pin "2") (pinfunction "2_2") (pintype "passive"))
    )
    (net (code "51") (name "Net-(Q1-G)") (class "Default")
      (node (ref "POWER") (pin "2") (pinfunction "2_2") (pintype "passive"))
      (node (ref "Q1") (pin "4") (pinfunction "G_4") (pintype "passive"))
      (node (ref "R12") (pin "1") (pinfunction "1_1") (pintype "passive"))
    )
    (net (code "52") (name "Net-(STM32F405RGT6-PB2{slash}BOOT1)") (class "Default")
      (node (ref "R1") (pin "2") (pinfunction "2_2") (pintype "passive"))
      (node (ref "STM32F405RGT6") (pin "28") (pinfunction "PB2/BOOT1_28") (pintype "bidirectional"))
    )
    (net (code "53") (name "Net-(STM32F405RGT6-VCAP_1)") (class "Default")
      (node (ref "C12") (pin "1") (pinfunction "1_1") (pintype "passive"))
      (node (ref "STM32F405RGT6") (pin "31") (pinfunction "VCAP_1_31") (pintype "power_in"))
    )
    (net (code "54") (name "Net-(STM32F405RGT6-VCAP_2)") (class "Default")
      (node (ref "C5") (pin "1") (pinfunction "1_1") (pintype "passive"))
      (node (ref "STM32F405RGT6") (pin "47") (pinfunction "VCAP_2_47") (pintype "power_in"))
    )
    (net (code "55") (name "Net-(U5-EN)") (class "Default")
      (node (ref "R7") (pin "1") (pinfunction "1_1") (pintype "passive"))
      (node (ref "U5") (pin "17") (pinfunction "EN_17") (pintype "input"))
    )
    (net (code "56") (name "Net-(U5-FB)") (class "Default")
      (node (ref "R8") (pin "1") (pinfunction "1_1") (pintype "passive"))
      (node (ref "R9") (pin "1") (pinfunction "1_1") (pintype "passive"))
      (node (ref "U5") (pin "1") (pinfunction "FB_1") (pintype "input"))
    )
    (net (code "57") (name "PC_RX") (class "Default")
      (node (ref "FT234X") (pin "4") (pinfunction "4_4") (pintype "passive"))
      (node (ref "STM32F405RGT6") (pin "42") (pinfunction "PA9_42") (pintype "bidirectional"))
    )
    (net (code "58") (name "PC_TX") (class "Default")
      (node (ref "FT234X") (pin "3") (pinfunction "3_3") (pintype "passive"))
      (node (ref "STM32F405RGT6") (pin "43") (pinfunction "PA10_43") (pintype "bidirectional"))
    )
    (net (code "59") (name "PUSH_IN_1") (class "Default")
      (node (ref "MODE") (pin "1") (pinfunction "1_1") (pintype "passive"))
      (node (ref "MODE") (pin "2") (pinfunction "2_2") (pintype "passive"))
      (node (ref "R3") (pin "1") (pinfunction "1_1") (pintype "passive"))
      (node (ref "STM32F405RGT6") (pin "9") (pinfunction "PC1_9") (pintype "bidirectional"))
    )
    (net (code "60") (name "RESET") (class "Default")
      (node (ref "C13") (pin "1") (pinfunction "1_1") (pintype "passive"))
      (node (ref "RESET") (pin "1") (pinfunction "1_1") (pintype "passive"))
      (node (ref "RESET") (pin "2") (pinfunction "2_2") (pintype "passive"))
      (node (ref "STM32F405RGT6") (pin "7") (pinfunction "NRST_7") (pintype "bidirectional"))
    )
    (net (code "61") (name "SCK") (class "Default")
      (node (ref "STM32F405RGT6") (pin "51") (pinfunction "PC10_51") (pintype "bidirectional"))
      (node (ref "TP6") (pin "TP") (pinfunction "TP_TP") (pintype "input"))
      (node (ref "U4") (pin "13") (pinfunction "SCL_13") (pintype "input"))
    )
    (net (code "62") (name "SENSOR_FL") (class "Default")
      (node (ref "PT_FL") (pin "K") (pinfunction "C_K") (pintype "passive"))
      (node (ref "R2FL") (pin "2") (pinfunction "2_2") (pintype "passive"))
      (node (ref "STM32F405RGT6") (pin "16") (pinfunction "PA2/USART2_TX_16") (pintype "bidirectional"))
    )
    (net (code "63") (name "SENSOR_FR") (class "Default")
      (node (ref "PT_FR") (pin "K") (pinfunction "C_K") (pintype "passive"))
      (node (ref "R2FR") (pin "2") (pinfunction "2_2") (pintype "passive"))
      (node (ref "STM32F405RGT6") (pin "14") (pinfunction "PA0/WKUP_14") (pintype "bidirectional"))
    )
    (net (code "64") (name "SENSOR_L") (class "Default")
      (node (ref "PT_L") (pin "K") (pinfunction "C_K") (pintype "passive"))
      (node (ref "R2L") (pin "2") (pinfunction "2_2") (pintype "passive"))
      (node (ref "STM32F405RGT6") (pin "17") (pinfunction "PA3/USART2_RX_17") (pintype "bidirectional"))
    )
    (net (code "65") (name "SENSOR_R") (class "Default")
      (node (ref "PT_R") (pin "K") (pinfunction "C_K") (pintype "passive"))
      (node (ref "R2R") (pin "2") (pinfunction "2_2") (pintype "passive"))
      (node (ref "STM32F405RGT6") (pin "15") (pinfunction "PA1/USART2_RTS_15") (pintype "bidirectional"))
    )
    (net (code "66") (name "SWCL") (class "Default")
      (node (ref "STM32F405RGT6") (pin "49") (pinfunction "PA14/JTCK-SWCLK_49") (pintype "bidirectional"))
    )
    (net (code "67") (name "SWDIO") (class "Default")
      (node (ref "STM32F405RGT6") (pin "46") (pinfunction "PA13/JMS-SWDIO_46") (pintype "bidirectional"))
    )
    (net (code "68") (name "VOL_CHECK") (class "Default")
      (node (ref "R4") (pin "1") (pinfunction "1_1") (pintype "passive"))
      (node (ref "R5") (pin "2") (pinfunction "2_2") (pintype "passive"))
      (node (ref "STM32F405RGT6") (pin "8") (pinfunction "PC0_8") (pintype "bidirectional"))
    )
    (net (code "69") (name "unconnected-(POWER-Pad3)") (class "Default")
      (node (ref "POWER") (pin "3") (pinfunction "3_3") (pintype "passive"))
    )
    (net (code "70") (name "unconnected-(STM32F405RGT6-PA4{slash}USART2_CK-Pad20)") (class "Default")
      (node (ref "STM32F405RGT6") (pin "20") (pinfunction "PA4/USART2_CK_20") (pintype "bidirectional"))
    )
    (net (code "71") (name "unconnected-(STM32F405RGT6-PA6{slash}SPI1_MISO-Pad22)") (class "Default")
      (node (ref "STM32F405RGT6") (pin "22") (pinfunction "PA6/SPI1_MISO_22") (pintype "bidirectional"))
    )
    (net (code "72") (name "unconnected-(STM32F405RGT6-PA8-Pad41)") (class "Default")
      (node (ref "STM32F405RGT6") (pin "41") (pinfunction "PA8_41") (pintype "bidirectional"))
    )
    (net (code "73") (name "unconnected-(STM32F405RGT6-PA11-Pad44)") (class "Default")
      (node (ref "STM32F405RGT6") (pin "44") (pinfunction "PA11_44") (pintype "bidirectional"))
    )
    (net (code "74") (name "unconnected-(STM32F405RGT6-PA12-Pad45)") (class "Default")
      (node (ref "STM32F405RGT6") (pin "45") (pinfunction "PA12_45") (pintype "bidirectional"))
    )
    (net (code "75") (name "unconnected-(STM32F405RGT6-PB0-Pad26)") (class "Default")
      (node (ref "STM32F405RGT6") (pin "26") (pinfunction "PB0_26") (pintype "bidirectional"))
    )
    (net (code "76") (name "unconnected-(STM32F405RGT6-PB1-Pad27)") (class "Default")
      (node (ref "STM32F405RGT6") (pin "27") (pinfunction "PB1_27") (pintype "bidirectional"))
    )
    (net (code "77") (name "unconnected-(STM32F405RGT6-PB8-Pad61)") (class "Default")
      (node (ref "STM32F405RGT6") (pin "61") (pinfunction "PB8_61") (pintype "bidirectional"))
    )
    (net (code "78") (name "unconnected-(STM32F405RGT6-PB9-Pad62)") (class "Default")
      (node (ref "STM32F405RGT6") (pin "62") (pinfunction "PB9_62") (pintype "bidirectional"))
    )
    (net (code "79") (name "unconnected-(STM32F405RGT6-PB12-Pad33)") (class "Default")
      (node (ref "STM32F405RGT6") (pin "33") (pinfunction "PB12_33") (pintype "bidirectional"))
    )
    (net (code "80") (name "unconnected-(STM32F405RGT6-PB13-Pad34)") (class "Default")
      (node (ref "STM32F405RGT6") (pin "34") (pinfunction "PB13_34") (pintype "bidirectional"))
    )
    (net (code "81") (name "unconnected-(STM32F405RGT6-PB14-Pad35)") (class "Default")
      (node (ref "STM32F405RGT6") (pin "35") (pinfunction "PB14_35") (pintype "bidirectional"))
    )
    (net (code "82") (name "unconnected-(STM32F405RGT6-PC2{slash}SPI2_MISO-Pad10)") (class "Default")
      (node (ref "STM32F405RGT6") (pin "10") (pinfunction "PC2/SPI2_MISO_10") (pintype "bidirectional"))
    )
    (net (code "83") (name "unconnected-(STM32F405RGT6-PC4-Pad24)") (class "Default")
      (node (ref "STM32F405RGT6") (pin "24") (pinfunction "PC4_24") (pintype "bidirectional"))
    )
    (net (code "84") (name "unconnected-(STM32F405RGT6-PC5-Pad25)") (class "Default")
      (node (ref "STM32F405RGT6") (pin "25") (pinfunction "PC5_25") (pintype "bidirectional"))
    )
    (net (code "85") (name "unconnected-(STM32F405RGT6-PC15{slash}OSC32_OUT-Pad4)") (class "Default")
      (node (ref "STM32F405RGT6") (pin "4") (pinfunction "PC15/OSC32_OUT_4") (pintype "bidirectional"))
    )
    (net (code "86") (name "unconnected-(STM32F405RGT6-PH0{slash}OSC_IN-Pad5)") (class "Default")
      (node (ref "STM32F405RGT6") (pin "5") (pinfunction "PH0/OSC_IN_5") (pintype "bidirectional"))
    )
    (net (code "87") (name "unconnected-(U2-CM1-Pad11)") (class "Default")
      (node (ref "U2") (pin "11") (pinfunction "CM1_11") (pintype "output"))
    )
    (net (code "88") (name "unconnected-(U2-CM2-Pad7)") (class "Default")
      (node (ref "U2") (pin "7") (pinfunction "CM2_7") (pintype "output"))
    )
    (net (code "89") (name "unconnected-(U2-NFAULT-Pad12)") (class "Default")
      (node (ref "U2") (pin "12") (pinfunction "NFAULT_12") (pintype "output"))
    )
    (net (code "90") (name "unconnected-(U3-CM1-Pad11)") (class "Default")
      (node (ref "U3") (pin "11") (pinfunction "CM1_11") (pintype "output"))
    )
    (net (code "91") (name "unconnected-(U3-CM2-Pad7)") (class "Default")
      (node (ref "U3") (pin "7") (pinfunction "CM2_7") (pintype "output"))
    )
    (net (code "92") (name "unconnected-(U3-NFAULT-Pad12)") (class "Default")
      (node (ref "U3") (pin "12") (pinfunction "NFAULT_12") (pintype "output"))
    )
    (net (code "93") (name "unconnected-(U4-INT1-Pad4)") (class "Default")
      (node (ref "U4") (pin "4") (pinfunction "INT1_4") (pintype "output"))
    )
    (net (code "94") (name "unconnected-(U4-INT2-Pad9)") (class "Default")
      (node (ref "U4") (pin "9") (pinfunction "INT2_9") (pintype "output"))
    )
    (net (code "95") (name "unconnected-(U4-OCS_AUX-Pad10)") (class "Default")
      (node (ref "U4") (pin "10") (pinfunction "OCS_AUX_10") (pintype "bidirectional"))
    )
    (net (code "96") (name "unconnected-(U4-SDO_AUX-Pad11)") (class "Default")
      (node (ref "U4") (pin "11") (pinfunction "SDO_AUX_11") (pintype "bidirectional"))
    )
    (net (code "97") (name "unconnected-(U5-AAM-Pad18)") (class "Default")
      (node (ref "U5") (pin "18") (pinfunction "AAM_18") (pintype "input"))
    )
    (net (code "98") (name "unconnected-(U5-BST-Pad11)") (class "Default")
      (node (ref "U5") (pin "11") (pinfunction "BST_11") (pintype "passive"))
    )
    (net (code "99") (name "unconnected-(U5-SW-Pad6)") (class "Default")
      (node (ref "U5") (pin "6") (pinfunction "SW_6") (pintype "output"))
    )
  )
)
